# Power_Unit.net
KiCad netlist of a schematic drawn in Altium Designer
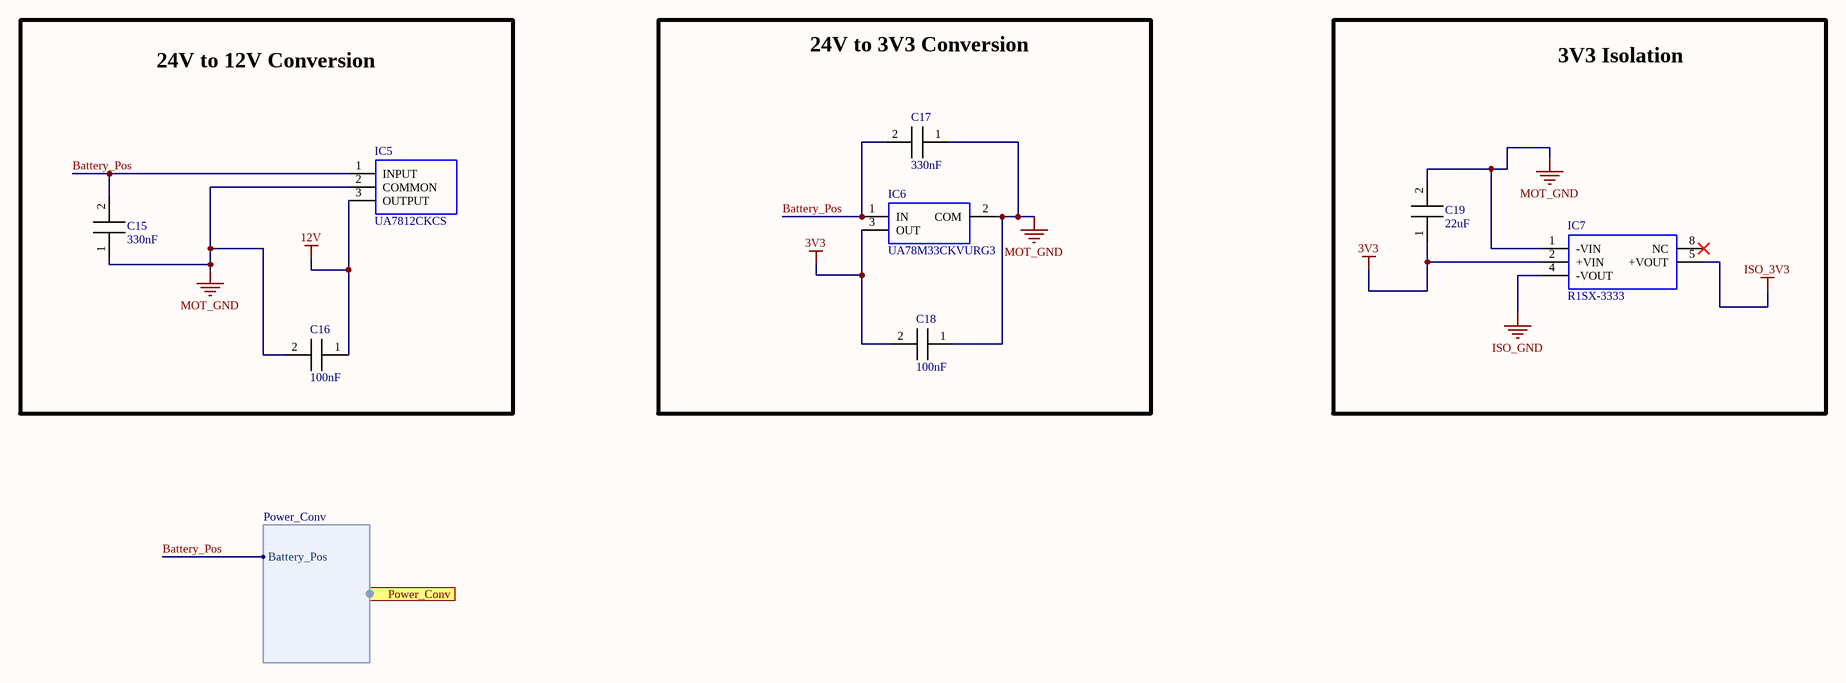
[diagram p0: Power_Unit.SchDoc]

(export (version "E")
  (design (tool "Eeschema 10.0.6"))
  (components
    (comp (ref "C15")
      (value "CAP 330nF")
      (footprint "0603_CAP")
      (fields (field (name "PARAMETER 1") "330nF"))
      (libsource (lib "Schlib1") (part "CAP 330nF"))
    )
    (comp (ref "C16")
      (value "CAP 100nF")
      (footprint "0603_CAP")
      (fields (field (name "PARAMETER 1") "100nF"))
      (libsource (lib "Schlib1") (part "CAP 100nF"))
    )
    (comp (ref "C17")
      (value "CAP 330nF")
      (footprint "0603_CAP")
      (fields (field (name "PARAMETER 1") "330nF"))
      (libsource (lib "Schlib1") (part "CAP 330nF"))
    )
    (comp (ref "C18")
      (value "CAP 100nF")
      (footprint "0603_CAP")
      (fields (field (name "PARAMETER 1") "100nF"))
      (libsource (lib "Schlib1") (part "CAP 100nF"))
    )
    (comp (ref "C19")
      (value "CAP  22uF")
      (footprint "0603_CAP")
      (fields (field (name "PARAMETER 1") "22uF"))
      (libsource (lib "Schlib1") (part "CAP  22uF"))
    )
    (comp (ref "IC5")
      (value "UA7812CKCS")
      (footprint "UA7812CKCS")
      (libsource (lib "Schlib1") (part "IC, LVR, UA7812CKCS"))
    )
    (comp (ref "IC6")
      (value "UA78M33CKVURG3")
      (footprint "UA78M33CKVURG3")
      (libsource (lib "Schlib1") (part "IC, LVR, UA78M33CKVURG3, 24/3V3"))
    )
    (comp (ref "IC7")
      (value "R1SX-3333")
      (footprint "R1SX_3333")
      (libsource (lib "Schlib1") (part "IC, DC/DC, ISO, R1SX-3333"))
    )
  )
  (nets
    (net (code "2") (name "/Battery_Pos") (class "Default")
      (node (ref "C15") (pin "2") (pinfunction "2_2") (pintype "passive"))
      (node (ref "C17") (pin "2") (pinfunction "2_2") (pintype "passive"))
      (node (ref "IC5") (pin "1") (pinfunction "INPUT_1") (pintype "passive"))
      (node (ref "IC6") (pin "1") (pinfunction "IN_1") (pintype "passive"))
    )
    (net (code "4") (name "3V3") (class "Default")
      (node (ref "C18") (pin "2") (pinfunction "2_2") (pintype "passive"))
      (node (ref "C19") (pin "1") (pinfunction "1_1") (pintype "passive"))
      (node (ref "IC6") (pin "3") (pinfunction "OUT_3") (pintype "passive"))
      (node (ref "IC7") (pin "2") (pinfunction "+VIN_2") (pintype "passive"))
    )
    (net (code "5") (name "12V") (class "Default")
      (node (ref "C16") (pin "1") (pinfunction "1_1") (pintype "passive"))
      (node (ref "IC5") (pin "3") (pinfunction "OUTPUT_3") (pintype "passive"))
    )
    (net (code "6") (name "ISO_3V3") (class "Default")
      (node (ref "IC7") (pin "5") (pinfunction "+VOUT_5") (pintype "passive"))
    )
    (net (code "7") (name "ISO_GND") (class "Default")
      (node (ref "IC7") (pin "4") (pinfunction "-VOUT_4") (pintype "passive"))
    )
    (net (code "8") (name "MOT_GND") (class "Default")
      (node (ref "C15") (pin "1") (pinfunction "1_1") (pintype "passive"))
      (node (ref "C16") (pin "2") (pinfunction "2_2") (pintype "passive"))
      (node (ref "C17") (pin "1") (pinfunction "1_1") (pintype "passive"))
      (node (ref "C18") (pin "1") (pinfunction "1_1") (pintype "passive"))
      (node (ref "C19") (pin "2") (pinfunction "2_2") (pintype "passive"))
      (node (ref "IC5") (pin "2") (pinfunction "COMMON_2") (pintype "passive"))
      (node (ref "IC6") (pin "2") (pinfunction "COM_2") (pintype "passive"))
      (node (ref "IC7") (pin "1") (pinfunction "-VIN_1") (pintype "passive"))
    )
    (net (code "9") (name "unconnected-(IC7-NC-Pad8)") (class "Default")
      (node (ref "IC7") (pin "8") (pinfunction "NC_8") (pintype "passive+no_connect"))
    )
  )
)
